# 6_Function_DCC_Decoder_V3.net
KiCad netlist of a schematic drawn in EAGLE
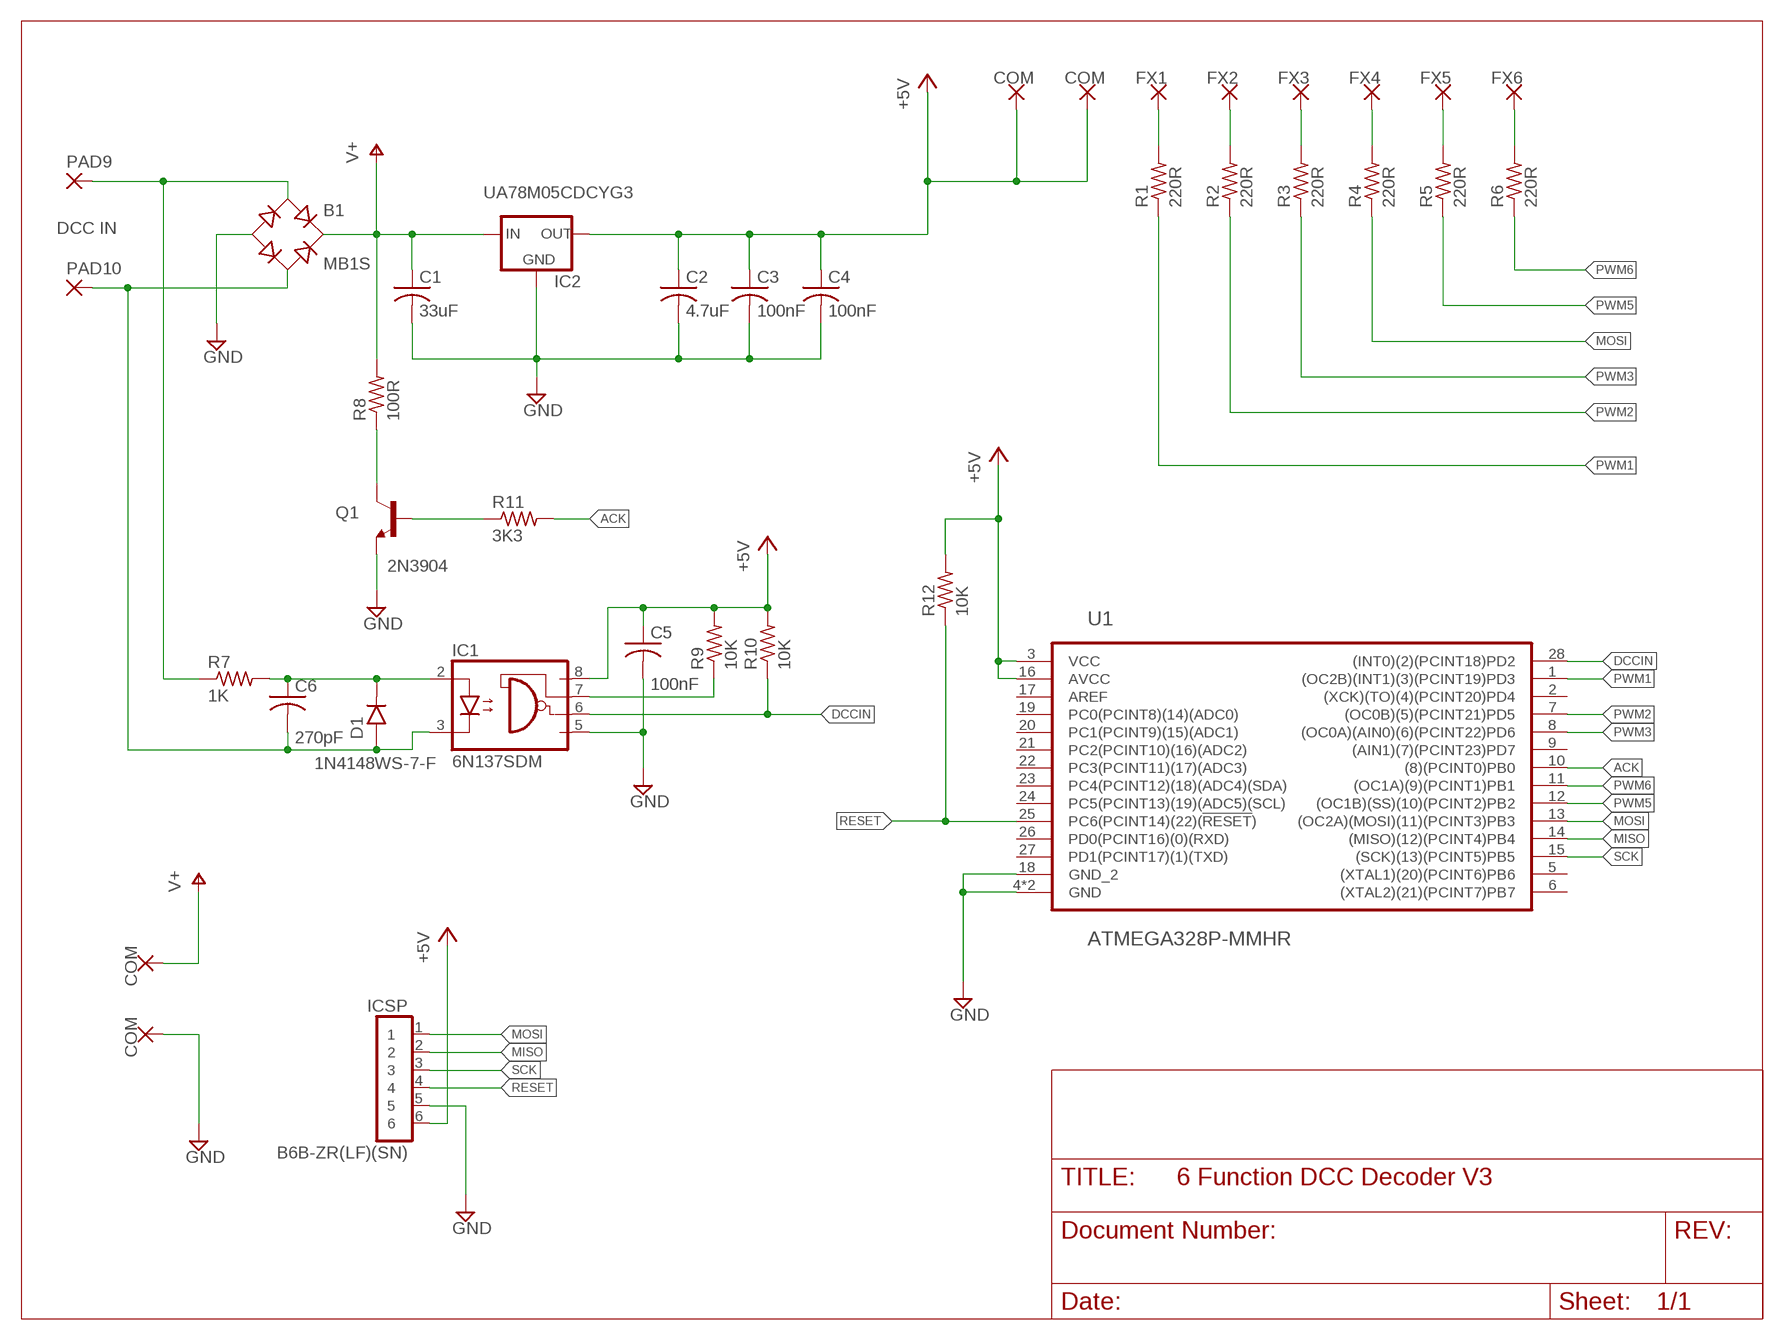
[diagram p0: schematic, sheet 1]

(export (version "E")
  (design (tool "Eeschema 10.0.6"))
  (components
    (comp (ref "B1")
      (value "MB1S")
      (footprint "eagle-import:SOIC-4")
      (libsource (lib "eagle-import") (part "MBS1"))
    )
    (comp (ref "C1")
      (value "33uF")
      (footprint "eagle-import:C1206")
      (libsource (lib "eagle-import") (part "C-USC1206"))
    )
    (comp (ref "C2")
      (value "4.7uF")
      (footprint "eagle-import:C0603K")
      (libsource (lib "eagle-import") (part "C-USC0603K"))
    )
    (comp (ref "C3")
      (value "100nF")
      (footprint "eagle-import:C0402K")
      (libsource (lib "eagle-import") (part "C-USC0402K"))
    )
    (comp (ref "C4")
      (value "100nF")
      (footprint "eagle-import:C0402K")
      (libsource (lib "eagle-import") (part "C-USC0402K"))
    )
    (comp (ref "C5")
      (value "100nF")
      (footprint "eagle-import:C0402K")
      (libsource (lib "eagle-import") (part "C-USC0402K"))
    )
    (comp (ref "C6")
      (value "270pF")
      (footprint "eagle-import:C0402K")
      (libsource (lib "eagle-import") (part "C-USC0402K"))
    )
    (comp (ref "D1")
      (value "1N4148WS-7-F")
      (footprint "eagle-import:SOD2513X120N")
      (fields (field (name "MANUFACTURER") "Diodes Inc."))
      (libsource (lib "eagle-import") (part "1N4148WS-7-F"))
    )
    (comp (ref "IC1")
      (value "6N137SDM")
      (footprint "eagle-import:SOP254P1030X508-8N")
      (fields (field (name "MOUSER_PART_NUMBER") "512-6N137SDM"))
      (libsource (lib "eagle-import") (part "6N137SDM"))
    )
    (comp (ref "IC2")
      (value "UA78M05CDCYG3")
      (footprint "eagle-import:SOT230P700X180-4N")
      (fields (field (name "MOUSER_PART_NUMBER") "595-UA78M05CDCYG3"))
      (libsource (lib "eagle-import") (part "UA78M05CDCYG3"))
    )
    (comp (ref "ICSP")
      (value "B6B-ZR(LF)(SN)")
      (footprint "eagle-import:JST_B6B-ZR(LF)(SN)")
      (fields (field (name "MF") "JST Sales") (field (name "MP") "B6B-ZR_LF__SN_"))
      (libsource (lib "eagle-import") (part "B6B-ZR(LF)(SN)"))
    )
    (comp (ref "PAD1")
      (value "FX1")
      (footprint "eagle-import:SMD1,27-2,54")
      (libsource (lib "eagle-import") (part "SMD2"))
    )
    (comp (ref "PAD2")
      (value "FX2")
      (footprint "eagle-import:SMD1,27-2,54")
      (libsource (lib "eagle-import") (part "SMD2"))
    )
    (comp (ref "PAD3")
      (value "FX3")
      (footprint "eagle-import:SMD1,27-2,54")
      (libsource (lib "eagle-import") (part "SMD2"))
    )
    (comp (ref "PAD4")
      (value "FX4")
      (footprint "eagle-import:SMD1,27-2,54")
      (libsource (lib "eagle-import") (part "SMD2"))
    )
    (comp (ref "PAD5")
      (value "FX5")
      (footprint "eagle-import:SMD1,27-2,54")
      (libsource (lib "eagle-import") (part "SMD2"))
    )
    (comp (ref "PAD6")
      (value "FX6")
      (footprint "eagle-import:SMD1,27-2,54")
      (libsource (lib "eagle-import") (part "SMD2"))
    )
    (comp (ref "PAD7")
      (value "COM")
      (footprint "eagle-import:SMD1,27-2,54")
      (libsource (lib "eagle-import") (part "SMD2"))
    )
    (comp (ref "PAD8")
      (value "COM")
      (footprint "eagle-import:SMD1,27-2,54")
      (libsource (lib "eagle-import") (part "SMD2"))
    )
    (comp (ref "PAD9")
      (value "SMD2")
      (footprint "eagle-import:SMD1,27-2,54")
      (libsource (lib "eagle-import") (part "SMD2"))
    )
    (comp (ref "PAD10")
      (value "SMD2")
      (footprint "eagle-import:SMD1,27-2,54")
      (libsource (lib "eagle-import") (part "SMD2"))
    )
    (comp (ref "PAD11")
      (value "COM")
      (footprint "eagle-import:SMD1,27-2,54")
      (libsource (lib "eagle-import") (part "SMD2"))
    )
    (comp (ref "PAD12")
      (value "COM")
      (footprint "eagle-import:SMD1,27-2,54")
      (libsource (lib "eagle-import") (part "SMD2"))
    )
    (comp (ref "Q1")
      (value "2N3904")
      (footprint "eagle-import:SOT23")
      (libsource (lib "eagle-import") (part "NPN-SOT23"))
    )
    (comp (ref "R1")
      (value "220R")
      (footprint "eagle-import:R0402")
      (libsource (lib "eagle-import") (part "R-US_R0402"))
    )
    (comp (ref "R2")
      (value "220R")
      (footprint "eagle-import:R0402")
      (libsource (lib "eagle-import") (part "R-US_R0402"))
    )
    (comp (ref "R3")
      (value "220R")
      (footprint "eagle-import:R0402")
      (libsource (lib "eagle-import") (part "R-US_R0402"))
    )
    (comp (ref "R4")
      (value "220R")
      (footprint "eagle-import:R0402")
      (libsource (lib "eagle-import") (part "R-US_R0402"))
    )
    (comp (ref "R5")
      (value "220R")
      (footprint "eagle-import:R0402")
      (libsource (lib "eagle-import") (part "R-US_R0402"))
    )
    (comp (ref "R6")
      (value "220R")
      (footprint "eagle-import:R0402")
      (libsource (lib "eagle-import") (part "R-US_R0402"))
    )
    (comp (ref "R7")
      (value "1K")
      (footprint "eagle-import:R0402")
      (libsource (lib "eagle-import") (part "R-US_R0402"))
    )
    (comp (ref "R8")
      (value "100R")
      (footprint "eagle-import:R1206")
      (libsource (lib "eagle-import") (part "R-US_R1206"))
    )
    (comp (ref "R9")
      (value "10K")
      (footprint "eagle-import:R0402")
      (libsource (lib "eagle-import") (part "R-US_R0402"))
    )
    (comp (ref "R10")
      (value "10K")
      (footprint "eagle-import:R0402")
      (libsource (lib "eagle-import") (part "R-US_R0402"))
    )
    (comp (ref "R11")
      (value "3K3")
      (footprint "eagle-import:R0402")
      (libsource (lib "eagle-import") (part "R-US_R0402"))
    )
    (comp (ref "R12")
      (value "10K")
      (footprint "eagle-import:R0402")
      (libsource (lib "eagle-import") (part "R-US_R0402"))
    )
    (comp (ref "U1")
      (value "ATMEGA328P-MMHR")
      (footprint "eagle-import:QFN45P400X400X100-29N")
      (libsource (lib "eagle-import") (part "ATMEGA328P-MMHR"))
    )
  )
  (nets
    (net (code "1") (name "+5V") (class "Default")
      (node (ref "C2") (pin "1") (pinfunction "1_1") (pintype "passive"))
      (node (ref "C3") (pin "1") (pinfunction "1_1") (pintype "passive"))
      (node (ref "C4") (pin "1") (pinfunction "1_1") (pintype "passive"))
      (node (ref "C5") (pin "1") (pinfunction "1_1") (pintype "passive"))
      (node (ref "IC1") (pin "8") (pinfunction "VCC_8") (pintype "passive"))
      (node (ref "IC2") (pin "3") (pinfunction "OUT_3") (pintype "passive"))
      (node (ref "ICSP") (pin "6") (pinfunction "6_6") (pintype "passive"))
      (node (ref "PAD7") (pin "1") (pinfunction "P_1") (pintype "passive"))
      (node (ref "PAD8") (pin "1") (pinfunction "P_1") (pintype "passive"))
      (node (ref "R10") (pin "2") (pinfunction "2_2") (pintype "passive"))
      (node (ref "R12") (pin "2") (pinfunction "2_2") (pintype "passive"))
      (node (ref "R9") (pin "2") (pinfunction "2_2") (pintype "passive"))
      (node (ref "U1") (pin "16") (pinfunction "AVCC_16") (pintype "power_in"))
      (node (ref "U1") (pin "3") (pinfunction "VCC_3") (pintype "power_in"))
    )
    (net (code "2") (name "ACK") (class "Default")
      (node (ref "R11") (pin "2") (pinfunction "2_2") (pintype "passive"))
      (node (ref "U1") (pin "10") (pinfunction "(8)(PCINT0)PB0_10") (pintype "bidirectional"))
    )
    (net (code "3") (name "DCCIN") (class "Default")
      (node (ref "IC1") (pin "6") (pinfunction "VO_6") (pintype "passive"))
      (node (ref "R10") (pin "1") (pinfunction "1_1") (pintype "passive"))
      (node (ref "U1") (pin "28") (pinfunction "(INT0)(2)(PCINT18)PD2_28") (pintype "bidirectional"))
    )
    (net (code "4") (name "GND") (class "Default")
      (node (ref "B1") (pin "-") (pinfunction "-_-") (pintype "passive"))
      (node (ref "C1") (pin "2") (pinfunction "2_2") (pintype "passive"))
      (node (ref "C2") (pin "2") (pinfunction "2_2") (pintype "passive"))
      (node (ref "C3") (pin "2") (pinfunction "2_2") (pintype "passive"))
      (node (ref "C4") (pin "2") (pinfunction "2_2") (pintype "passive"))
      (node (ref "C5") (pin "2") (pinfunction "2_2") (pintype "passive"))
      (node (ref "IC1") (pin "5") (pinfunction "GND_5") (pintype "passive"))
      (node (ref "IC2") (pin "2") (pinfunction "GND_2") (pintype "input"))
      (node (ref "IC2") (pin "4") (pinfunction "GND_4") (pintype "input"))
      (node (ref "ICSP") (pin "5") (pinfunction "5_5") (pintype "passive"))
      (node (ref "PAD12") (pin "1") (pinfunction "P_1") (pintype "passive"))
      (node (ref "Q1") (pin "2") (pinfunction "E_2") (pintype "passive"))
      (node (ref "U1") (pin "18") (pinfunction "GND_2_18") (pintype "passive"))
      (node (ref "U1") (pin "29") (pinfunction "GND_29") (pintype "passive"))
      (node (ref "U1") (pin "4") (pinfunction "GND_4") (pintype "passive"))
    )
    (net (code "5") (name "MISO") (class "Default")
      (node (ref "ICSP") (pin "2") (pinfunction "2_2") (pintype "passive"))
      (node (ref "U1") (pin "14") (pinfunction "(MISO)(12)(PCINT4)PB4_14") (pintype "bidirectional"))
    )
    (net (code "6") (name "MOSI") (class "Default")
      (node (ref "ICSP") (pin "1") (pinfunction "1_1") (pintype "passive"))
      (node (ref "R4") (pin "1") (pinfunction "1_1") (pintype "passive"))
      (node (ref "U1") (pin "13") (pinfunction "(OC2A)(MOSI)(11)(PCINT3)PB3_13") (pintype "bidirectional"))
    )
    (net (code "7") (name "Net-(B1-AC1)") (class "Default")
      (node (ref "B1") (pin "~1") (pinfunction "AC1_~1") (pintype "passive"))
      (node (ref "PAD9") (pin "1") (pinfunction "P_1") (pintype "passive"))
      (node (ref "R7") (pin "1") (pinfunction "1_1") (pintype "passive"))
    )
    (net (code "8") (name "Net-(B1-AC2)") (class "Default")
      (node (ref "B1") (pin "~2") (pinfunction "AC2_~2") (pintype "passive"))
      (node (ref "C6") (pin "2") (pinfunction "2_2") (pintype "passive"))
      (node (ref "D1") (pin "A") (pinfunction "A_A") (pintype "passive"))
      (node (ref "IC1") (pin "3") (pinfunction "C_3") (pintype "passive"))
      (node (ref "PAD10") (pin "1") (pinfunction "P_1") (pintype "passive"))
    )
    (net (code "9") (name "Net-(IC1-A)") (class "Default")
      (node (ref "C6") (pin "1") (pinfunction "1_1") (pintype "passive"))
      (node (ref "D1") (pin "C") (pinfunction "C_C") (pintype "passive"))
      (node (ref "IC1") (pin "2") (pinfunction "A_2") (pintype "passive"))
      (node (ref "R7") (pin "2") (pinfunction "2_2") (pintype "passive"))
    )
    (net (code "10") (name "Net-(IC1-VE)") (class "Default")
      (node (ref "IC1") (pin "7") (pinfunction "VE_7") (pintype "passive"))
      (node (ref "R9") (pin "1") (pinfunction "1_1") (pintype "passive"))
    )
    (net (code "11") (name "Net-(PAD1-P)") (class "Default")
      (node (ref "PAD1") (pin "1") (pinfunction "P_1") (pintype "passive"))
      (node (ref "R1") (pin "2") (pinfunction "2_2") (pintype "passive"))
    )
    (net (code "12") (name "Net-(PAD2-P)") (class "Default")
      (node (ref "PAD2") (pin "1") (pinfunction "P_1") (pintype "passive"))
      (node (ref "R2") (pin "2") (pinfunction "2_2") (pintype "passive"))
    )
    (net (code "13") (name "Net-(PAD3-P)") (class "Default")
      (node (ref "PAD3") (pin "1") (pinfunction "P_1") (pintype "passive"))
      (node (ref "R3") (pin "2") (pinfunction "2_2") (pintype "passive"))
    )
    (net (code "14") (name "Net-(PAD4-P)") (class "Default")
      (node (ref "PAD4") (pin "1") (pinfunction "P_1") (pintype "passive"))
      (node (ref "R4") (pin "2") (pinfunction "2_2") (pintype "passive"))
    )
    (net (code "15") (name "Net-(PAD5-P)") (class "Default")
      (node (ref "PAD5") (pin "1") (pinfunction "P_1") (pintype "passive"))
      (node (ref "R5") (pin "2") (pinfunction "2_2") (pintype "passive"))
    )
    (net (code "16") (name "Net-(PAD6-P)") (class "Default")
      (node (ref "PAD6") (pin "1") (pinfunction "P_1") (pintype "passive"))
      (node (ref "R6") (pin "2") (pinfunction "2_2") (pintype "passive"))
    )
    (net (code "17") (name "Net-(Q1-B)") (class "Default")
      (node (ref "Q1") (pin "1") (pinfunction "B_1") (pintype "passive"))
      (node (ref "R11") (pin "1") (pinfunction "1_1") (pintype "passive"))
    )
    (net (code "18") (name "Net-(Q1-C)") (class "Default")
      (node (ref "Q1") (pin "3") (pinfunction "C_3") (pintype "passive"))
      (node (ref "R8") (pin "1") (pinfunction "1_1") (pintype "passive"))
    )
    (net (code "19") (name "PWM1") (class "Default")
      (node (ref "R1") (pin "1") (pinfunction "1_1") (pintype "passive"))
      (node (ref "U1") (pin "1") (pinfunction "(OC2B)(INT1)(3)(PCINT19)PD3_1") (pintype "bidirectional"))
    )
    (net (code "20") (name "PWM2") (class "Default")
      (node (ref "R2") (pin "1") (pinfunction "1_1") (pintype "passive"))
      (node (ref "U1") (pin "7") (pinfunction "(OC0B)(5)(PCINT21)PD5_7") (pintype "bidirectional"))
    )
    (net (code "21") (name "PWM3") (class "Default")
      (node (ref "R3") (pin "1") (pinfunction "1_1") (pintype "passive"))
      (node (ref "U1") (pin "8") (pinfunction "(OC0A)(AIN0)(6)(PCINT22)PD6_8") (pintype "bidirectional"))
    )
    (net (code "22") (name "PWM5") (class "Default")
      (node (ref "R5") (pin "1") (pinfunction "1_1") (pintype "passive"))
      (node (ref "U1") (pin "12") (pinfunction "(OC1B)(SS)(10)(PCINT2)PB2_12") (pintype "bidirectional"))
    )
    (net (code "23") (name "PWM6") (class "Default")
      (node (ref "R6") (pin "1") (pinfunction "1_1") (pintype "passive"))
      (node (ref "U1") (pin "11") (pinfunction "(OC1A)(9)(PCINT1)PB1_11") (pintype "bidirectional"))
    )
    (net (code "24") (name "RESET") (class "Default")
      (node (ref "ICSP") (pin "4") (pinfunction "4_4") (pintype "passive"))
      (node (ref "R12") (pin "1") (pinfunction "1_1") (pintype "passive"))
      (node (ref "U1") (pin "25") (pinfunction "PC6(PCINT14)(22)(~{RESET})_25") (pintype "bidirectional"))
    )
    (net (code "25") (name "SCK") (class "Default")
      (node (ref "ICSP") (pin "3") (pinfunction "3_3") (pintype "passive"))
      (node (ref "U1") (pin "15") (pinfunction "(SCK)(13)(PCINT5)PB5_15") (pintype "bidirectional"))
    )
    (net (code "26") (name "V+") (class "Default")
      (node (ref "B1") (pin "+") (pinfunction "+_+") (pintype "passive"))
      (node (ref "C1") (pin "1") (pinfunction "1_1") (pintype "passive"))
      (node (ref "IC2") (pin "1") (pinfunction "IN_1") (pintype "input"))
      (node (ref "PAD11") (pin "1") (pinfunction "P_1") (pintype "passive"))
      (node (ref "R8") (pin "2") (pinfunction "2_2") (pintype "passive"))
    )
    (net (code "27") (name "unconnected-(U1-(AIN1)(7)(PCINT23)PD7-Pad9)") (class "Default")
      (node (ref "U1") (pin "9") (pinfunction "(AIN1)(7)(PCINT23)PD7_9") (pintype "bidirectional"))
    )
    (net (code "28") (name "unconnected-(U1-(XCK)(TO)(4)(PCINT20)PD4-Pad2)") (class "Default")
      (node (ref "U1") (pin "2") (pinfunction "(XCK)(TO)(4)(PCINT20)PD4_2") (pintype "bidirectional"))
    )
    (net (code "29") (name "unconnected-(U1-(XTAL1)(20)(PCINT6)PB6-Pad5)") (class "Default")
      (node (ref "U1") (pin "5") (pinfunction "(XTAL1)(20)(PCINT6)PB6_5") (pintype "bidirectional"))
    )
    (net (code "30") (name "unconnected-(U1-(XTAL2)(21)(PCINT7)PB7-Pad6)") (class "Default")
      (node (ref "U1") (pin "6") (pinfunction "(XTAL2)(21)(PCINT7)PB7_6") (pintype "bidirectional"))
    )
    (net (code "31") (name "unconnected-(U1-AREF-Pad17)") (class "Default")
      (node (ref "U1") (pin "17") (pinfunction "AREF_17") (pintype "input"))
    )
    (net (code "32") (name "unconnected-(U1-PC0(PCINT8)(14)(ADC0)-Pad19)") (class "Default")
      (node (ref "U1") (pin "19") (pinfunction "PC0(PCINT8)(14)(ADC0)_19") (pintype "bidirectional"))
    )
    (net (code "33") (name "unconnected-(U1-PC1(PCINT9)(15)(ADC1)-Pad20)") (class "Default")
      (node (ref "U1") (pin "20") (pinfunction "PC1(PCINT9)(15)(ADC1)_20") (pintype "bidirectional"))
    )
    (net (code "34") (name "unconnected-(U1-PC2(PCINT10)(16)(ADC2)-Pad21)") (class "Default")
      (node (ref "U1") (pin "21") (pinfunction "PC2(PCINT10)(16)(ADC2)_21") (pintype "bidirectional"))
    )
    (net (code "35") (name "unconnected-(U1-PC3(PCINT11)(17)(ADC3)-Pad22)") (class "Default")
      (node (ref "U1") (pin "22") (pinfunction "PC3(PCINT11)(17)(ADC3)_22") (pintype "bidirectional"))
    )
    (net (code "36") (name "unconnected-(U1-PC4(PCINT12)(18)(ADC4)(SDA)-Pad23)") (class "Default")
      (node (ref "U1") (pin "23") (pinfunction "PC4(PCINT12)(18)(ADC4)(SDA)_23") (pintype "bidirectional"))
    )
    (net (code "37") (name "unconnected-(U1-PC5(PCINT13)(19)(ADC5)(SCL)-Pad24)") (class "Default")
      (node (ref "U1") (pin "24") (pinfunction "PC5(PCINT13)(19)(ADC5)(SCL)_24") (pintype "bidirectional"))
    )
    (net (code "38") (name "unconnected-(U1-PD0(PCINT16)(0)(RXD)-Pad26)") (class "Default")
      (node (ref "U1") (pin "26") (pinfunction "PD0(PCINT16)(0)(RXD)_26") (pintype "bidirectional"))
    )
    (net (code "39") (name "unconnected-(U1-PD1(PCINT17)(1)(TXD)-Pad27)") (class "Default")
      (node (ref "U1") (pin "27") (pinfunction "PD1(PCINT17)(1)(TXD)_27") (pintype "bidirectional"))
    )
  )
)
